# ComsPCB_1P.net
KiCad netlist of a schematic drawn in EAGLE
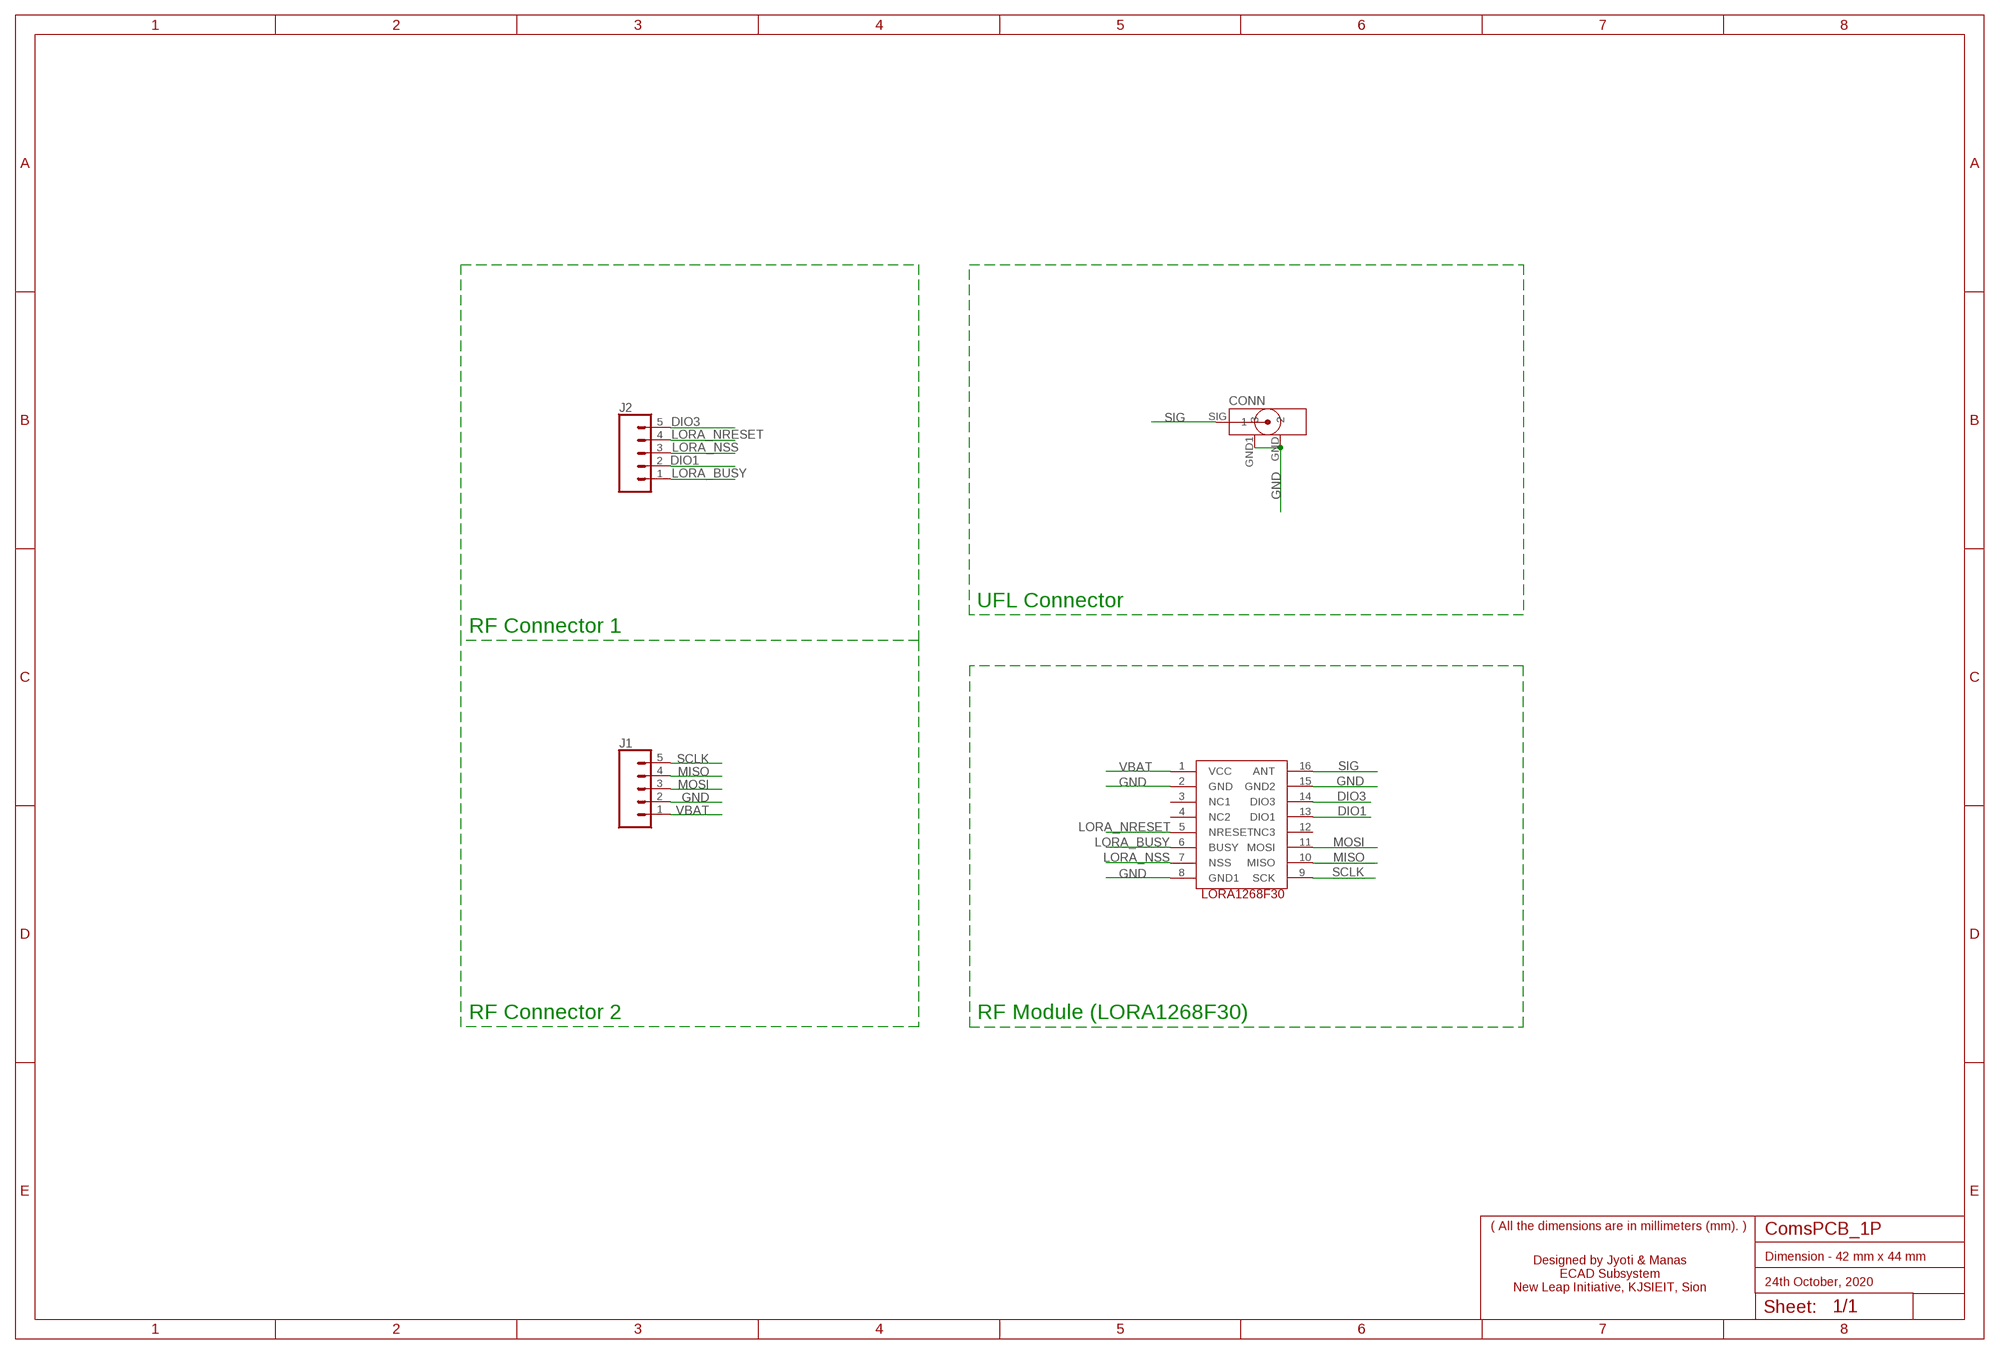
[diagram p0: schematic, sheet 1]

(export (version "E")
  (design (tool "Eeschema 10.0.6"))
  (components
    (comp (ref "CONN")
      (value "U.FL-R-SMT(10)")
      (footprint "eagle-import:U.FL-R-SMT(10)")
      (fields
        (field (name "DIGIKEY_PART_NUMBER") "H9161CT-ND")
        (field (name "MANUFACTURER") "Hirose Electric Co Ltd")
        (field (name "CREATED_BY") "PCBLayout.com")
      )
      (libsource (lib "eagle-import") (part "U.FL-R-SMT(10)"))
    )
    (comp (ref "J1")
      (value "CONN_051.27MM")
      (footprint "eagle-import:1X05_1.27MM")
      (libsource (lib "eagle-import") (part "CONN_051.27MM"))
    )
    (comp (ref "J2")
      (value "CONN_051.27MM")
      (footprint "eagle-import:1X05_1.27MM")
      (libsource (lib "eagle-import") (part "CONN_051.27MM"))
    )
    (comp (ref "U$1")
      (value "U1")
      (footprint "eagle-import:LORA1268F30")
      (libsource (lib "eagle-import") (part "LORA1268F30"))
    )
  )
  (nets
    (net (code "1") (name "/DIO1") (class "Default")
      (node (ref "J2") (pin "2") (pinfunction "2_2") (pintype "passive"))
      (node (ref "U$1") (pin "13") (pinfunction "DIO1_13") (pintype "bidirectional"))
    )
    (net (code "2") (name "/DIO3") (class "Default")
      (node (ref "J2") (pin "5") (pinfunction "5_5") (pintype "passive"))
      (node (ref "U$1") (pin "14") (pinfunction "DIO3_14") (pintype "bidirectional"))
    )
    (net (code "3") (name "/GND") (class "Default")
      (node (ref "CONN") (pin "GND") (pinfunction "2_GND") (pintype "passive"))
      (node (ref "CONN") (pin "GND1") (pinfunction "3_GND1") (pintype "passive"))
      (node (ref "J1") (pin "2") (pinfunction "2_2") (pintype "passive"))
      (node (ref "U$1") (pin "15") (pinfunction "GND2_15") (pintype "bidirectional"))
      (node (ref "U$1") (pin "2") (pinfunction "GND_2") (pintype "bidirectional"))
      (node (ref "U$1") (pin "8") (pinfunction "GND1_8") (pintype "bidirectional"))
    )
    (net (code "4") (name "/LORA_BUSY") (class "Default")
      (node (ref "J2") (pin "1") (pinfunction "1_1") (pintype "passive"))
      (node (ref "U$1") (pin "6") (pinfunction "BUSY_6") (pintype "bidirectional"))
    )
    (net (code "5") (name "/LORA_NRESET") (class "Default")
      (node (ref "J2") (pin "4") (pinfunction "4_4") (pintype "passive"))
      (node (ref "U$1") (pin "5") (pinfunction "NRESET_5") (pintype "bidirectional"))
    )
    (net (code "6") (name "/LORA_NSS") (class "Default")
      (node (ref "J2") (pin "3") (pinfunction "3_3") (pintype "passive"))
      (node (ref "U$1") (pin "7") (pinfunction "NSS_7") (pintype "bidirectional"))
    )
    (net (code "7") (name "/MISO") (class "Default")
      (node (ref "J1") (pin "4") (pinfunction "4_4") (pintype "passive"))
      (node (ref "U$1") (pin "10") (pinfunction "MISO_10") (pintype "bidirectional"))
    )
    (net (code "8") (name "/MOSI") (class "Default")
      (node (ref "J1") (pin "3") (pinfunction "3_3") (pintype "passive"))
      (node (ref "U$1") (pin "11") (pinfunction "MOSI_11") (pintype "bidirectional"))
    )
    (net (code "9") (name "/SCLK") (class "Default")
      (node (ref "J1") (pin "5") (pinfunction "5_5") (pintype "passive"))
      (node (ref "U$1") (pin "9") (pinfunction "SCK_9") (pintype "bidirectional"))
    )
    (net (code "10") (name "/SIG") (class "Default")
      (node (ref "CONN") (pin "SIG") (pinfunction "1_SIG") (pintype "passive"))
      (node (ref "U$1") (pin "16") (pinfunction "ANT_16") (pintype "bidirectional"))
    )
    (net (code "11") (name "/VBAT") (class "Default")
      (node (ref "J1") (pin "1") (pinfunction "1_1") (pintype "passive"))
      (node (ref "U$1") (pin "1") (pinfunction "VCC_1") (pintype "bidirectional"))
    )
    (net (code "12") (name "unconnected-(U$1-NC1-Pad3)") (class "Default")
      (node (ref "U$1") (pin "3") (pinfunction "NC1_3") (pintype "bidirectional"))
    )
    (net (code "13") (name "unconnected-(U$1-NC2-Pad4)") (class "Default")
      (node (ref "U$1") (pin "4") (pinfunction "NC2_4") (pintype "bidirectional"))
    )
    (net (code "14") (name "unconnected-(U$1-NC3-Pad12)") (class "Default")
      (node (ref "U$1") (pin "12") (pinfunction "NC3_12") (pintype "bidirectional"))
    )
  )
)
